# main-01.net
KiCad netlist of a schematic drawn in EAGLE
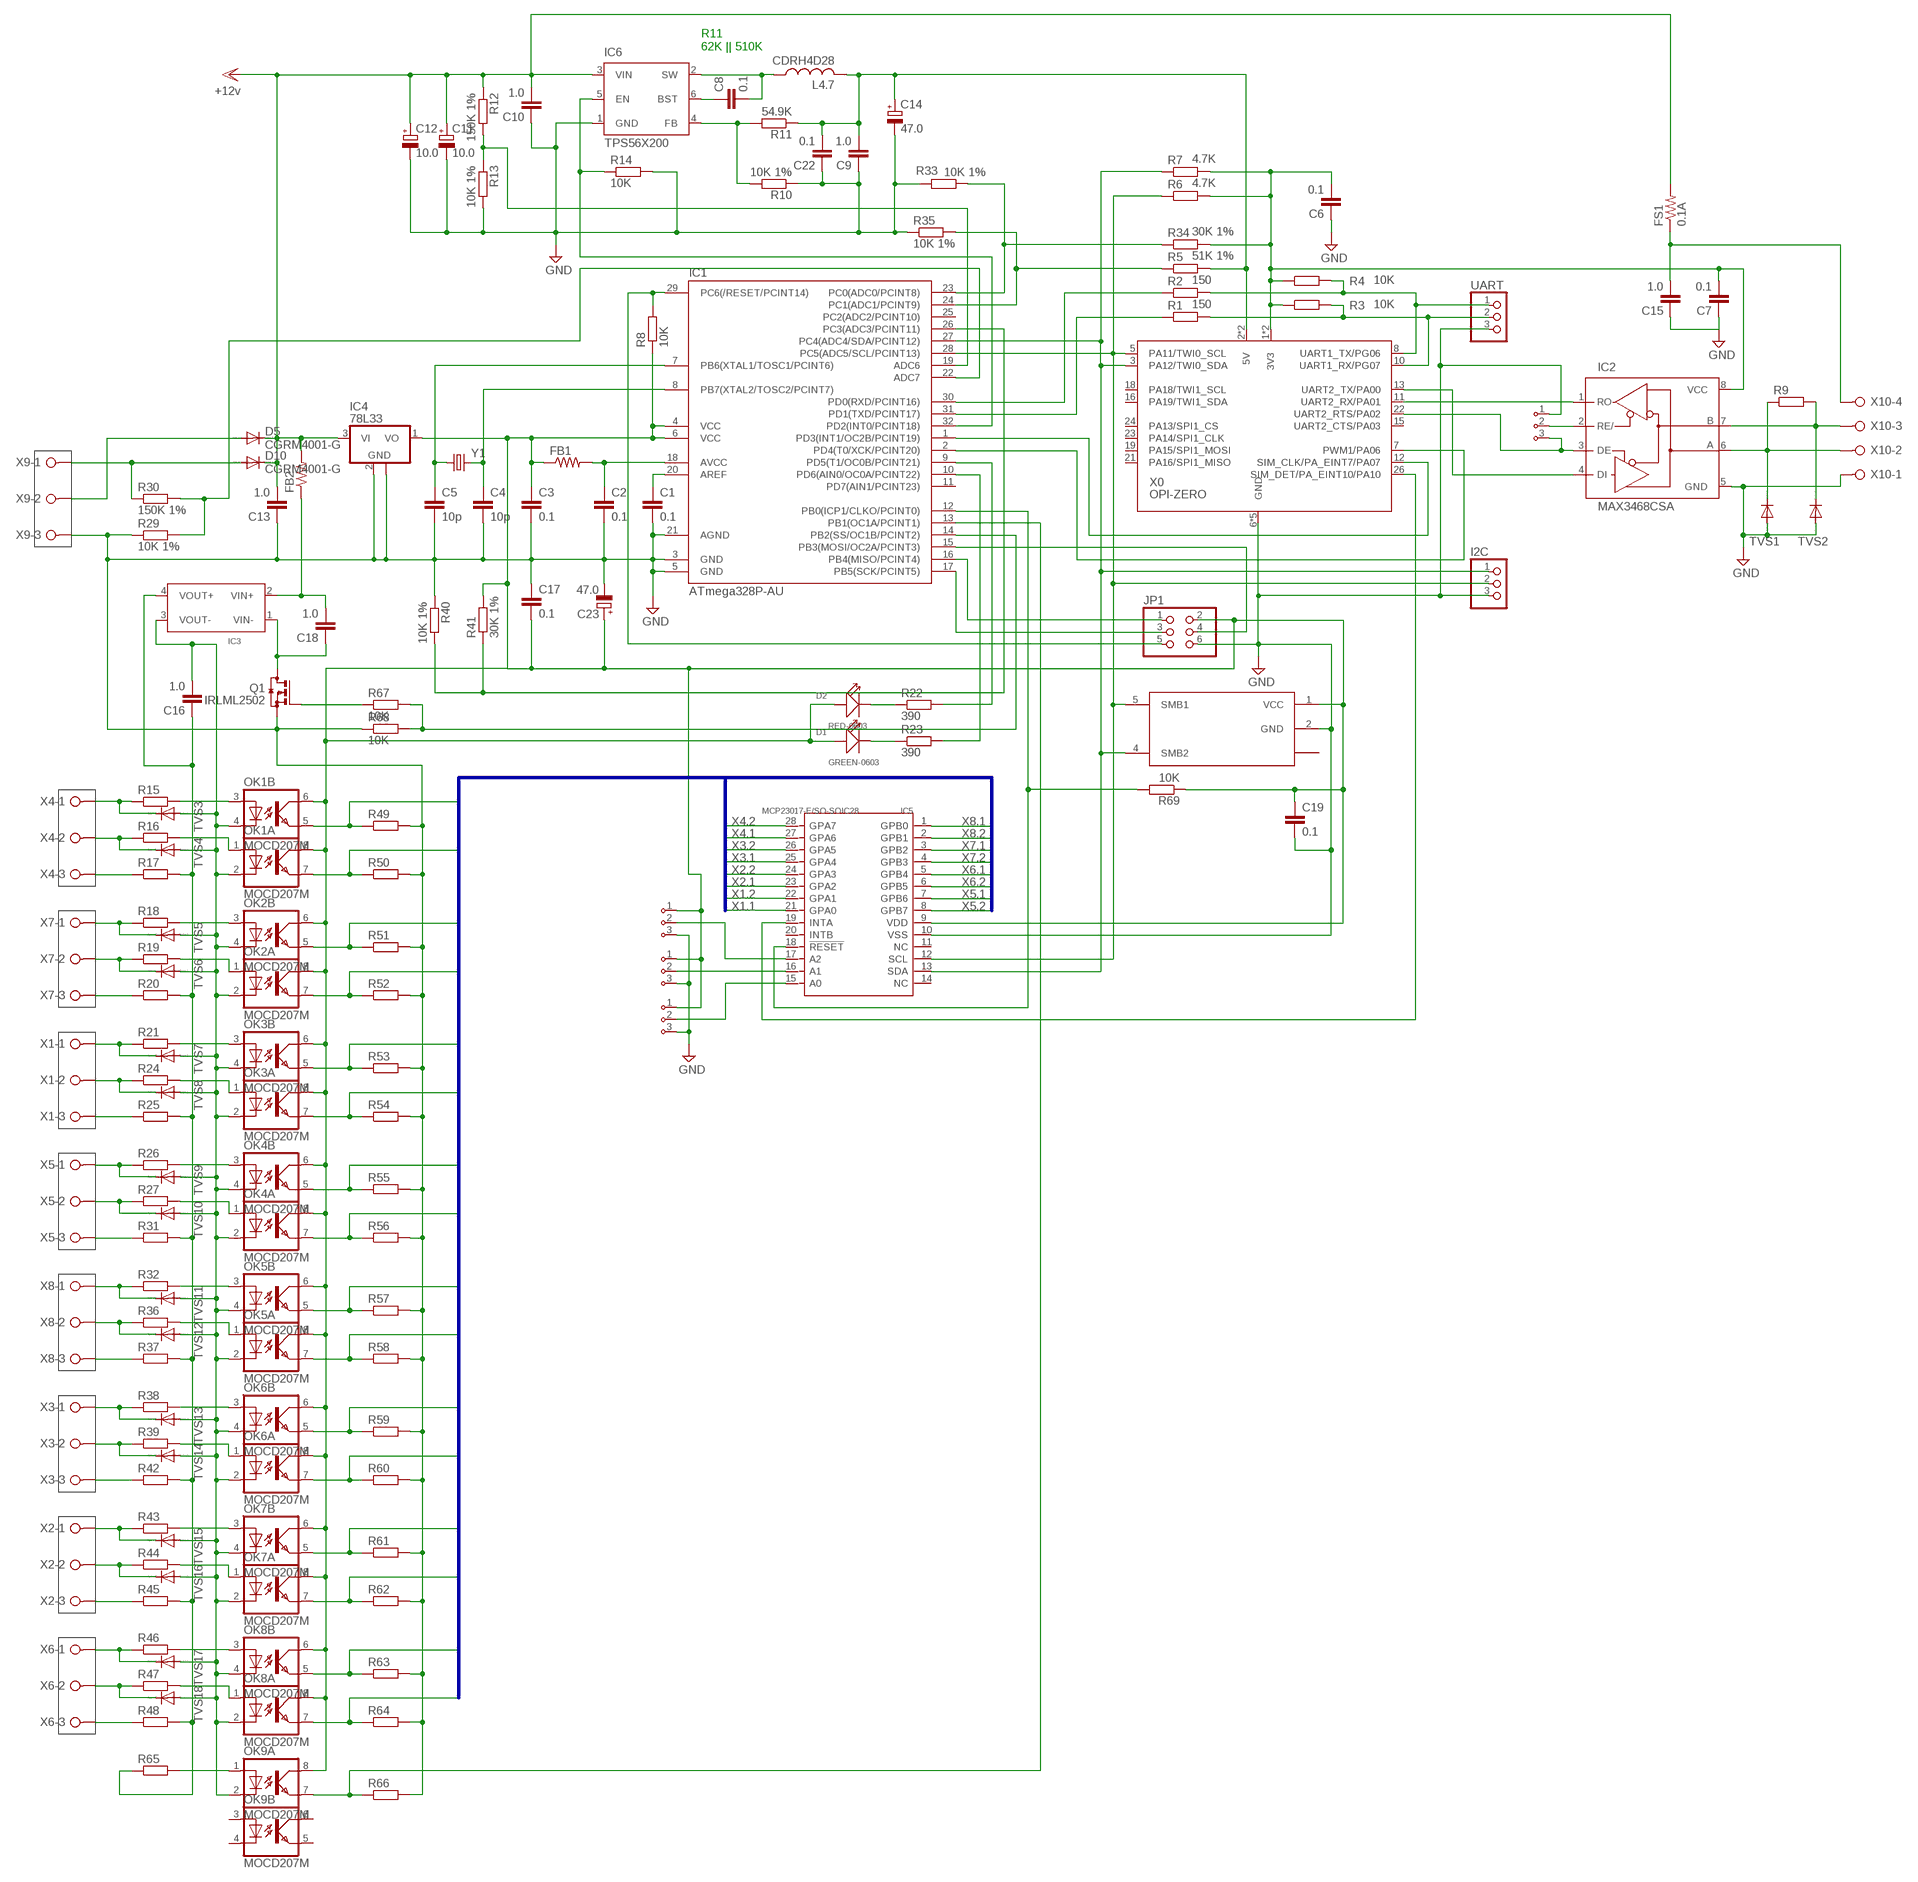
[diagram p0: schematic, sheet 1]

(export (version "E")
  (design (tool "Eeschema 10.0.6"))
  (components
    (comp (ref "4")
      (value "ADDR3PIN0603")
      (footprint "eagle-import:0603-3PIN")
      (libsource (lib "eagle-import") (part "ADDR3PIN0603"))
    )
    (comp (ref "A0")
      (value "ADDR3PIN0603")
      (footprint "eagle-import:0603-3PIN")
      (libsource (lib "eagle-import") (part "ADDR3PIN0603"))
    )
    (comp (ref "A1")
      (value "ADDR3PIN0603")
      (footprint "eagle-import:0603-3PIN")
      (libsource (lib "eagle-import") (part "ADDR3PIN0603"))
    )
    (comp (ref "A2")
      (value "ADDR3PIN0603")
      (footprint "eagle-import:0603-3PIN")
      (libsource (lib "eagle-import") (part "ADDR3PIN0603"))
    )
    (comp (ref "C1")
      (value "0.1")
      (footprint "eagle-import:C0603")
      (libsource (lib "eagle-import") (part "C-EUC0603"))
    )
    (comp (ref "C2")
      (value "0.1")
      (footprint "eagle-import:C0603")
      (libsource (lib "eagle-import") (part "C-EUC0603"))
    )
    (comp (ref "C3")
      (value "0.1")
      (footprint "eagle-import:C0603")
      (libsource (lib "eagle-import") (part "C-EUC0603"))
    )
    (comp (ref "C4")
      (value "10p")
      (footprint "eagle-import:C0603")
      (libsource (lib "eagle-import") (part "C-EUC0603"))
    )
    (comp (ref "C5")
      (value "10p")
      (footprint "eagle-import:C0603")
      (libsource (lib "eagle-import") (part "C-EUC0603"))
    )
    (comp (ref "C6")
      (value "0.1")
      (footprint "eagle-import:C0805")
      (libsource (lib "eagle-import") (part "C-EUC0805"))
    )
    (comp (ref "C7")
      (value "0.1")
      (footprint "eagle-import:C0805")
      (libsource (lib "eagle-import") (part "C-EUC0805"))
    )
    (comp (ref "C8")
      (value "0.1")
      (footprint "eagle-import:C0805")
      (libsource (lib "eagle-import") (part "C-EUC0805"))
    )
    (comp (ref "C9")
      (value "1.0")
      (footprint "eagle-import:C0805")
      (libsource (lib "eagle-import") (part "C-EUC0805"))
    )
    (comp (ref "C10")
      (value "1.0")
      (footprint "eagle-import:C1206")
      (libsource (lib "eagle-import") (part "C-EUC1206"))
    )
    (comp (ref "C11")
      (value "10.0")
      (footprint "eagle-import:C_6032-28R")
      (libsource (lib "eagle-import") (part "CPOL-EUC/6032-28R"))
    )
    (comp (ref "C12")
      (value "10.0")
      (footprint "eagle-import:C_6032-28R")
      (libsource (lib "eagle-import") (part "CPOL-EUC/6032-28R"))
    )
    (comp (ref "C13")
      (value "1.0")
      (footprint "eagle-import:C1206")
      (libsource (lib "eagle-import") (part "C-EUC1206"))
    )
    (comp (ref "C14")
      (value "47.0")
      (footprint "eagle-import:B_3528-21R")
      (libsource (lib "eagle-import") (part "CPOL-EUB/3528-21R"))
    )
    (comp (ref "C15")
      (value "1.0")
      (footprint "eagle-import:C1206")
      (libsource (lib "eagle-import") (part "C-EUC1206"))
    )
    (comp (ref "C16")
      (value "1.0")
      (footprint "eagle-import:C1206")
      (libsource (lib "eagle-import") (part "C-EUC1206"))
    )
    (comp (ref "C17")
      (value "0.1")
      (footprint "eagle-import:C0603")
      (libsource (lib "eagle-import") (part "C-EUC0603"))
    )
    (comp (ref "C18")
      (value "1.0")
      (footprint "eagle-import:C1206")
      (libsource (lib "eagle-import") (part "C-EUC1206"))
    )
    (comp (ref "C19")
      (value "0.1")
      (footprint "eagle-import:C0603")
      (libsource (lib "eagle-import") (part "C-EUC0603"))
    )
    (comp (ref "C22")
      (value "0.1")
      (footprint "eagle-import:C0805")
      (libsource (lib "eagle-import") (part "C-EUC0805"))
    )
    (comp (ref "C23")
      (value "47.0")
      (footprint "eagle-import:B_3528-21R")
      (libsource (lib "eagle-import") (part "CPOL-EUB/3528-21R"))
    )
    (comp (ref "D1")
      (value "GREEN-0603")
      (footprint "eagle-import:LED-0603")
      (fields (field (name "MPN") "19-217-G7C-AN1P2-3T"))
      (libsource (lib "eagle-import") (part "SMD-LED-CLEAR-GREEN(0603)"))
    )
    (comp (ref "D2")
      (value "RED-0603")
      (footprint "eagle-import:LED-0603")
      (fields (field (name "MPN") "19-217-BHC-ZL1M2RY-3T"))
      (libsource (lib "eagle-import") (part "SMD-LED-CLEAR-BLUE(0603)"))
    )
    (comp (ref "D5")
      (value "CGRM4001-G")
      (footprint "eagle-import:SOD-123_MINI-SMA")
      (libsource (lib "eagle-import") (part "CGRM400-G1"))
    )
    (comp (ref "D10")
      (value "CGRM4001-G")
      (footprint "eagle-import:SOD-123_MINI-SMA")
      (libsource (lib "eagle-import") (part "CGRM400-G1"))
    )
    (comp (ref "FB1")
      (value "R-US_R0805")
      (footprint "eagle-import:R0805")
      (libsource (lib "eagle-import") (part "R-US_R0805"))
    )
    (comp (ref "FB2")
      (value "R-US_R1206")
      (footprint "eagle-import:R1206")
      (libsource (lib "eagle-import") (part "R-US_R1206"))
    )
    (comp (ref "FS1")
      (value "0.1A")
      (footprint "eagle-import:R1210")
      (libsource (lib "eagle-import") (part "R-US_R1210"))
    )
    (comp (ref "I2C")
      (value "PINHD-1X3")
      (footprint "eagle-import:1X03")
      (libsource (lib "eagle-import") (part "PINHD-1X3"))
    )
    (comp (ref "IC1")
      (value "ATmega328P-AU")
      (footprint "eagle-import:TQFP32-08")
      (libsource (lib "eagle-import") (part "MEGA48/88/168-AU"))
    )
    (comp (ref "IC2")
      (value "MAX3468CSA")
      (footprint "eagle-import:SO08")
      (fields (field (name "MPN") "MAX3468CSA+"))
      (libsource (lib "eagle-import") (part "MAX34SA68C"))
    )
    (comp (ref "IC3")
      (value "DC-DC-CONV-4PIN-ISOLATINGMURATA-NME-05-12-SERIES")
      (footprint "eagle-import:DC-DC-MURATA-NME-05-12-SERIES")
      (libsource (lib "eagle-import") (part "DC-DC-CONV-4PIN-ISOLATINGMURATA-NME-05-12-SERIES"))
    )
    (comp (ref "IC4")
      (value "78L33")
      (footprint "eagle-import:SOT89")
      (libsource (lib "eagle-import") (part "78LF05"))
    )
    (comp (ref "IC5")
      (value "MCP23017-E/SO-SOIC28")
      (footprint "eagle-import:SOIC28-1.27-17.9X7.5MM")
      (fields (field (name "MPN") "MCP23017-E/SO"))
      (libsource (lib "eagle-import") (part "INTERFACE-MCP23017-E(SOIC28)"))
    )
    (comp (ref "IC6")
      (value "TPS56X200")
      (footprint "eagle-import:TSOT23-6_DDC")
      (libsource (lib "eagle-import") (part "TPS56X200"))
    )
    (comp (ref "IC7")
      (value "LTC1694")
      (footprint "eagle-import:SOT23-5")
      (libsource (lib "eagle-import") (part "LTC1694"))
    )
    (comp (ref "JP1")
      (value "PINHD-2X3")
      (footprint "eagle-import:2X03")
      (libsource (lib "eagle-import") (part "PINHD-2X3"))
    )
    (comp (ref "L4.7")
      (value "CDRH4D28")
      (footprint "eagle-import:CDRH4D28")
      (libsource (lib "eagle-import") (part "CDRH4D28"))
    )
    (comp (ref "OK1")
      (value "MOCD207M")
      (footprint "eagle-import:SOIC08-FAIRCHILD")
      (fields (field (name "MF") "FAIRCHILD SEMICONDUCTOR") (field (name "MPN") "MOCD207-M"))
      (libsource (lib "eagle-import") (part "MOCD20M7"))
    )
    (comp (ref "OK2")
      (value "MOCD207M")
      (footprint "eagle-import:SOIC08-FAIRCHILD")
      (fields (field (name "MF") "FAIRCHILD SEMICONDUCTOR") (field (name "MPN") "MOCD207-M"))
      (libsource (lib "eagle-import") (part "MOCD20M7"))
    )
    (comp (ref "OK3")
      (value "MOCD207M")
      (footprint "eagle-import:SOIC08-FAIRCHILD")
      (fields (field (name "MF") "FAIRCHILD SEMICONDUCTOR") (field (name "MPN") "MOCD207-M"))
      (libsource (lib "eagle-import") (part "MOCD20M7"))
    )
    (comp (ref "OK4")
      (value "MOCD207M")
      (footprint "eagle-import:SOIC08-FAIRCHILD")
      (fields (field (name "MF") "FAIRCHILD SEMICONDUCTOR") (field (name "MPN") "MOCD207-M"))
      (libsource (lib "eagle-import") (part "MOCD20M7"))
    )
    (comp (ref "OK5")
      (value "MOCD207M")
      (footprint "eagle-import:SOIC08-FAIRCHILD")
      (fields (field (name "MF") "FAIRCHILD SEMICONDUCTOR") (field (name "MPN") "MOCD207-M"))
      (libsource (lib "eagle-import") (part "MOCD20M7"))
    )
    (comp (ref "OK6")
      (value "MOCD207M")
      (footprint "eagle-import:SOIC08-FAIRCHILD")
      (fields (field (name "MF") "FAIRCHILD SEMICONDUCTOR") (field (name "MPN") "MOCD207-M"))
      (libsource (lib "eagle-import") (part "MOCD20M7"))
    )
    (comp (ref "OK7")
      (value "MOCD207M")
      (footprint "eagle-import:SOIC08-FAIRCHILD")
      (fields (field (name "MF") "FAIRCHILD SEMICONDUCTOR") (field (name "MPN") "MOCD207-M"))
      (libsource (lib "eagle-import") (part "MOCD20M7"))
    )
    (comp (ref "OK8")
      (value "MOCD207M")
      (footprint "eagle-import:SOIC08-FAIRCHILD")
      (fields (field (name "MF") "FAIRCHILD SEMICONDUCTOR") (field (name "MPN") "MOCD207-M"))
      (libsource (lib "eagle-import") (part "MOCD20M7"))
    )
    (comp (ref "OK9")
      (value "MOCD207M")
      (footprint "eagle-import:SOIC08-FAIRCHILD")
      (fields (field (name "MF") "FAIRCHILD SEMICONDUCTOR") (field (name "MPN") "MOCD207-M"))
      (libsource (lib "eagle-import") (part "MOCD20M7"))
    )
    (comp (ref "Q1")
      (value "IRLML2502")
      (footprint "eagle-import:SOT23")
      (libsource (lib "eagle-import") (part "IRLML2502"))
    )
    (comp (ref "R1")
      (value "150")
      (footprint "eagle-import:R0603")
      (libsource (lib "eagle-import") (part "R-EU_R0603"))
    )
    (comp (ref "R2")
      (value "150")
      (footprint "eagle-import:R0603")
      (libsource (lib "eagle-import") (part "R-EU_R0603"))
    )
    (comp (ref "R3")
      (value "10K")
      (footprint "eagle-import:R0603")
      (libsource (lib "eagle-import") (part "R-EU_R0603"))
    )
    (comp (ref "R4")
      (value "10K")
      (footprint "eagle-import:R0603")
      (libsource (lib "eagle-import") (part "R-EU_R0603"))
    )
    (comp (ref "R5")
      (value "51K 1%")
      (footprint "eagle-import:R0603")
      (libsource (lib "eagle-import") (part "R-EU_R0603"))
    )
    (comp (ref "R6")
      (value "4.7K")
      (footprint "eagle-import:R0603")
      (libsource (lib "eagle-import") (part "R-EU_R0603"))
    )
    (comp (ref "R7")
      (value "4.7K")
      (footprint "eagle-import:R0603")
      (libsource (lib "eagle-import") (part "R-EU_R0603"))
    )
    (comp (ref "R8")
      (value "10K")
      (footprint "eagle-import:R0603")
      (libsource (lib "eagle-import") (part "R-EU_R0603"))
    )
    (comp (ref "R9")
      (value "R-EU_R1206")
      (footprint "eagle-import:R1206")
      (libsource (lib "eagle-import") (part "R-EU_R1206"))
    )
    (comp (ref "R10")
      (value "10K 1%")
      (footprint "eagle-import:R0603")
      (libsource (lib "eagle-import") (part "R-EU_R0603"))
    )
    (comp (ref "R11")
      (value "54.9K")
      (footprint "eagle-import:R0603")
      (libsource (lib "eagle-import") (part "R-EU_R0603"))
    )
    (comp (ref "R12")
      (value "150K 1%")
      (footprint "eagle-import:R0603")
      (libsource (lib "eagle-import") (part "R-EU_R0603"))
    )
    (comp (ref "R13")
      (value "10K 1%")
      (footprint "eagle-import:R0603")
      (libsource (lib "eagle-import") (part "R-EU_R0603"))
    )
    (comp (ref "R14")
      (value "10K")
      (footprint "eagle-import:R0603")
      (libsource (lib "eagle-import") (part "R-EU_R0603"))
    )
    (comp (ref "R15")
      (value "R-EU_R0603")
      (footprint "eagle-import:R0603")
      (libsource (lib "eagle-import") (part "R-EU_R0603"))
    )
    (comp (ref "R16")
      (value "R-EU_R0603")
      (footprint "eagle-import:R0603")
      (libsource (lib "eagle-import") (part "R-EU_R0603"))
    )
    (comp (ref "R17")
      (value "R-EU_R0603")
      (footprint "eagle-import:R0603")
      (libsource (lib "eagle-import") (part "R-EU_R0603"))
    )
    (comp (ref "R18")
      (value "R-EU_R0603")
      (footprint "eagle-import:R0603")
      (libsource (lib "eagle-import") (part "R-EU_R0603"))
    )
    (comp (ref "R19")
      (value "R-EU_R0603")
      (footprint "eagle-import:R0603")
      (libsource (lib "eagle-import") (part "R-EU_R0603"))
    )
    (comp (ref "R20")
      (value "R-EU_R0603")
      (footprint "eagle-import:R0603")
      (libsource (lib "eagle-import") (part "R-EU_R0603"))
    )
    (comp (ref "R21")
      (value "R-EU_R0603")
      (footprint "eagle-import:R0603")
      (libsource (lib "eagle-import") (part "R-EU_R0603"))
    )
    (comp (ref "R22")
      (value "390")
      (footprint "eagle-import:R0603")
      (libsource (lib "eagle-import") (part "R-EU_R0603"))
    )
    (comp (ref "R23")
      (value "390")
      (footprint "eagle-import:R0603")
      (libsource (lib "eagle-import") (part "R-EU_R0603"))
    )
    (comp (ref "R24")
      (value "R-EU_R0603")
      (footprint "eagle-import:R0603")
      (libsource (lib "eagle-import") (part "R-EU_R0603"))
    )
    (comp (ref "R25")
      (value "R-EU_R0603")
      (footprint "eagle-import:R0603")
      (libsource (lib "eagle-import") (part "R-EU_R0603"))
    )
    (comp (ref "R26")
      (value "R-EU_R0603")
      (footprint "eagle-import:R0603")
      (libsource (lib "eagle-import") (part "R-EU_R0603"))
    )
    (comp (ref "R27")
      (value "R-EU_R0603")
      (footprint "eagle-import:R0603")
      (libsource (lib "eagle-import") (part "R-EU_R0603"))
    )
    (comp (ref "R29")
      (value "10K 1%")
      (footprint "eagle-import:R0603")
      (libsource (lib "eagle-import") (part "R-EU_R0603"))
    )
    (comp (ref "R30")
      (value "150K 1%")
      (footprint "eagle-import:R0603")
      (libsource (lib "eagle-import") (part "R-EU_R0603"))
    )
    (comp (ref "R31")
      (value "R-EU_R0603")
      (footprint "eagle-import:R0603")
      (libsource (lib "eagle-import") (part "R-EU_R0603"))
    )
    (comp (ref "R32")
      (value "R-EU_R0603")
      (footprint "eagle-import:R0603")
      (libsource (lib "eagle-import") (part "R-EU_R0603"))
    )
    (comp (ref "R33")
      (value "10K 1%")
      (footprint "eagle-import:R0603")
      (libsource (lib "eagle-import") (part "R-EU_R0603"))
    )
    (comp (ref "R34")
      (value "30K 1%")
      (footprint "eagle-import:R0603")
      (libsource (lib "eagle-import") (part "R-EU_R0603"))
    )
    (comp (ref "R35")
      (value "10K 1%")
      (footprint "eagle-import:R0603")
      (libsource (lib "eagle-import") (part "R-EU_R0603"))
    )
    (comp (ref "R36")
      (value "R-EU_R0603")
      (footprint "eagle-import:R0603")
      (libsource (lib "eagle-import") (part "R-EU_R0603"))
    )
    (comp (ref "R37")
      (value "R-EU_R0603")
      (footprint "eagle-import:R0603")
      (libsource (lib "eagle-import") (part "R-EU_R0603"))
    )
    (comp (ref "R38")
      (value "R-EU_R0603")
      (footprint "eagle-import:R0603")
      (libsource (lib "eagle-import") (part "R-EU_R0603"))
    )
    (comp (ref "R39")
      (value "R-EU_R0603")
      (footprint "eagle-import:R0603")
      (libsource (lib "eagle-import") (part "R-EU_R0603"))
    )
    (comp (ref "R40")
      (value "10K 1%")
      (footprint "eagle-import:R0603")
      (libsource (lib "eagle-import") (part "R-EU_R0603"))
    )
    (comp (ref "R41")
      (value "30K 1%")
      (footprint "eagle-import:R0603")
      (libsource (lib "eagle-import") (part "R-EU_R0603"))
    )
    (comp (ref "R42")
      (value "R-EU_R0603")
      (footprint "eagle-import:R0603")
      (libsource (lib "eagle-import") (part "R-EU_R0603"))
    )
    (comp (ref "R43")
      (value "R-EU_R0603")
      (footprint "eagle-import:R0603")
      (libsource (lib "eagle-import") (part "R-EU_R0603"))
    )
    (comp (ref "R44")
      (value "R-EU_R0603")
      (footprint "eagle-import:R0603")
      (libsource (lib "eagle-import") (part "R-EU_R0603"))
    )
    (comp (ref "R45")
      (value "R-EU_R0603")
      (footprint "eagle-import:R0603")
      (libsource (lib "eagle-import") (part "R-EU_R0603"))
    )
    (comp (ref "R46")
      (value "R-EU_R0603")
      (footprint "eagle-import:R0603")
      (libsource (lib "eagle-import") (part "R-EU_R0603"))
    )
    (comp (ref "R47")
      (value "R-EU_R0603")
      (footprint "eagle-import:R0603")
      (libsource (lib "eagle-import") (part "R-EU_R0603"))
    )
    (comp (ref "R48")
      (value "R-EU_R0603")
      (footprint "eagle-import:R0603")
      (libsource (lib "eagle-import") (part "R-EU_R0603"))
    )
    (comp (ref "R49")
      (value "R-EU_R0603")
      (footprint "eagle-import:R0603")
      (libsource (lib "eagle-import") (part "R-EU_R0603"))
    )
    (comp (ref "R50")
      (value "R-EU_R0603")
      (footprint "eagle-import:R0603")
      (libsource (lib "eagle-import") (part "R-EU_R0603"))
    )
    (comp (ref "R51")
      (value "R-EU_R0603")
      (footprint "eagle-import:R0603")
      (libsource (lib "eagle-import") (part "R-EU_R0603"))
    )
    (comp (ref "R52")
      (value "R-EU_R0603")
      (footprint "eagle-import:R0603")
      (libsource (lib "eagle-import") (part "R-EU_R0603"))
    )
    (comp (ref "R53")
      (value "R-EU_R0603")
      (footprint "eagle-import:R0603")
      (libsource (lib "eagle-import") (part "R-EU_R0603"))
    )
    (comp (ref "R54")
      (value "R-EU_R0603")
      (footprint "eagle-import:R0603")
      (libsource (lib "eagle-import") (part "R-EU_R0603"))
    )
    (comp (ref "R55")
      (value "R-EU_R0603")
      (footprint "eagle-import:R0603")
      (libsource (lib "eagle-import") (part "R-EU_R0603"))
    )
    (comp (ref "R56")
      (value "R-EU_R0603")
      (footprint "eagle-import:R0603")
      (libsource (lib "eagle-import") (part "R-EU_R0603"))
    )
    (comp (ref "R57")
      (value "R-EU_R0603")
      (footprint "eagle-import:R0603")
      (libsource (lib "eagle-import") (part "R-EU_R0603"))
    )
    (comp (ref "R58")
      (value "R-EU_R0603")
      (footprint "eagle-import:R0603")
      (libsource (lib "eagle-import") (part "R-EU_R0603"))
    )
    (comp (ref "R59")
      (value "R-EU_R0603")
      (footprint "eagle-import:R0603")
      (libsource (lib "eagle-import") (part "R-EU_R0603"))
    )
    (comp (ref "R60")
      (value "R-EU_R0603")
      (footprint "eagle-import:R0603")
      (libsource (lib "eagle-import") (part "R-EU_R0603"))
    )
    (comp (ref "R61")
      (value "R-EU_R0603")
      (footprint "eagle-import:R0603")
      (libsource (lib "eagle-import") (part "R-EU_R0603"))
    )
    (comp (ref "R62")
      (value "R-EU_R0603")
      (footprint "eagle-import:R0603")
      (libsource (lib "eagle-import") (part "R-EU_R0603"))
    )
    (comp (ref "R63")
      (value "R-EU_R0603")
      (footprint "eagle-import:R0603")
      (libsource (lib "eagle-import") (part "R-EU_R0603"))
    )
    (comp (ref "R64")
      (value "R-EU_R0603")
      (footprint "eagle-import:R0603")
      (libsource (lib "eagle-import") (part "R-EU_R0603"))
    )
    (comp (ref "R65")
      (value "R-EU_R0603")
      (footprint "eagle-import:R0603")
      (libsource (lib "eagle-import") (part "R-EU_R0603"))
    )
    (comp (ref "R66")
      (value "R-EU_R0603")
      (footprint "eagle-import:R0603")
      (libsource (lib "eagle-import") (part "R-EU_R0603"))
    )
    (comp (ref "R67")
      (value "10K")
      (footprint "eagle-import:R0603")
      (libsource (lib "eagle-import") (part "R-EU_R0603"))
    )
    (comp (ref "R68")
      (value "10K")
      (footprint "eagle-import:R0603")
      (libsource (lib "eagle-import") (part "R-EU_R0603"))
    )
    (comp (ref "R69")
      (value "10K")
      (footprint "eagle-import:R0603")
      (libsource (lib "eagle-import") (part "R-EU_R0603"))
    )
    (comp (ref "TVS1")
      (value "DIODE-SOD323-W")
      (footprint "eagle-import:SOD323-W")
      (libsource (lib "eagle-import") (part "DIODE-SOD323-W"))
    )
    (comp (ref "TVS2")
      (value "DIODE-SOD323-W")
      (footprint "eagle-import:SOD323-W")
      (libsource (lib "eagle-import") (part "DIODE-SOD323-W"))
    )
    (comp (ref "TVS3")
      (value "DIODE-SOD323-W")
      (footprint "eagle-import:SOD323-W")
      (libsource (lib "eagle-import") (part "DIODE-SOD323-W"))
    )
    (comp (ref "TVS4")
      (value "DIODE-SOD323-W")
      (footprint "eagle-import:SOD323-W")
      (libsource (lib "eagle-import") (part "DIODE-SOD323-W"))
    )
    (comp (ref "TVS5")
      (value "DIODE-SOD323-W")
      (footprint "eagle-import:SOD323-W")
      (libsource (lib "eagle-import") (part "DIODE-SOD323-W"))
    )
    (comp (ref "TVS6")
      (value "DIODE-SOD323-W")
      (footprint "eagle-import:SOD323-W")
      (libsource (lib "eagle-import") (part "DIODE-SOD323-W"))
    )
    (comp (ref "TVS7")
      (value "DIODE-SOD323-W")
      (footprint "eagle-import:SOD323-W")
      (libsource (lib "eagle-import") (part "DIODE-SOD323-W"))
    )
    (comp (ref "TVS8")
      (value "DIODE-SOD323-W")
      (footprint "eagle-import:SOD323-W")
      (libsource (lib "eagle-import") (part "DIODE-SOD323-W"))
    )
    (comp (ref "TVS9")
      (value "DIODE-SOD323-W")
      (footprint "eagle-import:SOD323-W")
      (libsource (lib "eagle-import") (part "DIODE-SOD323-W"))
    )
    (comp (ref "TVS10")
      (value "DIODE-SOD323-W")
      (footprint "eagle-import:SOD323-W")
      (libsource (lib "eagle-import") (part "DIODE-SOD323-W"))
    )
    (comp (ref "TVS11")
      (value "DIODE-SOD323-W")
      (footprint "eagle-import:SOD323-W")
      (libsource (lib "eagle-import") (part "DIODE-SOD323-W"))
    )
    (comp (ref "TVS12")
      (value "DIODE-SOD323-W")
      (footprint "eagle-import:SOD323-W")
      (libsource (lib "eagle-import") (part "DIODE-SOD323-W"))
    )
    (comp (ref "TVS13")
      (value "DIODE-SOD323-W")
      (footprint "eagle-import:SOD323-W")
      (libsource (lib "eagle-import") (part "DIODE-SOD323-W"))
    )
    (comp (ref "TVS14")
      (value "DIODE-SOD323-W")
      (footprint "eagle-import:SOD323-W")
      (libsource (lib "eagle-import") (part "DIODE-SOD323-W"))
    )
    (comp (ref "TVS15")
      (value "DIODE-SOD323-W")
      (footprint "eagle-import:SOD323-W")
      (libsource (lib "eagle-import") (part "DIODE-SOD323-W"))
    )
    (comp (ref "TVS16")
      (value "DIODE-SOD323-W")
      (footprint "eagle-import:SOD323-W")
      (libsource (lib "eagle-import") (part "DIODE-SOD323-W"))
    )
    (comp (ref "TVS17")
      (value "DIODE-SOD323-W")
      (footprint "eagle-import:SOD323-W")
      (libsource (lib "eagle-import") (part "DIODE-SOD323-W"))
    )
    (comp (ref "TVS18")
      (value "DIODE-SOD323-W")
      (footprint "eagle-import:SOD323-W")
      (libsource (lib "eagle-import") (part "DIODE-SOD323-W"))
    )
    (comp (ref "UART")
      (value "PINHD-1X3")
      (footprint "eagle-import:1X03")
      (libsource (lib "eagle-import") (part "PINHD-1X3"))
    )
    (comp (ref "X0")
      (value "OPI-ZERO")
      (footprint "eagle-import:OPI0")
      (libsource (lib "eagle-import") (part "OPI-ZERO"))
    )
    (comp (ref "X1")
      (value "W237-03P")
      (footprint "eagle-import:W237-133")
      (libsource (lib "eagle-import") (part "W237-03P"))
    )
    (comp (ref "X2")
      (value "W237-03P")
      (footprint "eagle-import:W237-133")
      (libsource (lib "eagle-import") (part "W237-03P"))
    )
    (comp (ref "X3")
      (value "W237-03P")
      (footprint "eagle-import:W237-133")
      (libsource (lib "eagle-import") (part "W237-03P"))
    )
    (comp (ref "X4")
      (value "W237-03P")
      (footprint "eagle-import:W237-133")
      (libsource (lib "eagle-import") (part "W237-03P"))
    )
    (comp (ref "X5")
      (value "W237-03P")
      (footprint "eagle-import:W237-133")
      (libsource (lib "eagle-import") (part "W237-03P"))
    )
    (comp (ref "X6")
      (value "W237-03P")
      (footprint "eagle-import:W237-133")
      (libsource (lib "eagle-import") (part "W237-03P"))
    )
    (comp (ref "X7")
      (value "W237-03P")
      (footprint "eagle-import:W237-133")
      (libsource (lib "eagle-import") (part "W237-03P"))
    )
    (comp (ref "X8")
      (value "W237-03P")
      (footprint "eagle-import:W237-133")
      (libsource (lib "eagle-import") (part "W237-03P"))
    )
    (comp (ref "X9")
      (value "W237-03P")
      (footprint "eagle-import:W237-133")
      (libsource (lib "eagle-import") (part "W237-03P"))
    )
    (comp (ref "X10")
      (value "W237-04P")
      (footprint "eagle-import:W237-4P")
      (libsource (lib "eagle-import") (part "W237-04P"))
    )
    (comp (ref "Y1")
      (value "CRYSTALHC49US")
      (footprint "eagle-import:HC49US")
      (libsource (lib "eagle-import") (part "CRYSTALHC49US"))
    )
  )
  (nets
    (net (code "1") (name "+12v") (class "Default")
      (node (ref "C10") (pin "2") (pinfunction "2_2") (pintype "passive"))
      (node (ref "C11") (pin "+") (pinfunction "+_+") (pintype "passive"))
      (node (ref "C12") (pin "+") (pinfunction "+_+") (pintype "passive"))
      (node (ref "C13") (pin "2") (pinfunction "2_2") (pintype "passive"))
      (node (ref "D10") (pin "C") (pinfunction "C_C") (pintype "passive"))
      (node (ref "D5") (pin "C") (pinfunction "C_C") (pintype "passive"))
      (node (ref "FB2") (pin "2") (pinfunction "2_2") (pintype "passive"))
      (node (ref "FS1") (pin "2") (pinfunction "2_2") (pintype "passive"))
      (node (ref "IC4") (pin "3") (pinfunction "VI_3") (pintype "input"))
      (node (ref "IC6") (pin "3") (pinfunction "VIN_3") (pintype "input"))
      (node (ref "R12") (pin "1") (pinfunction "1_1") (pintype "passive"))
    )
    (net (code "2") (name "/X1.1") (class "Default")
      (node (ref "IC5") (pin "21") (pinfunction "GPA0_21") (pintype "bidirectional"))
      (node (ref "OK3") (pin "5") (pinfunction "EMIT_5") (pintype "passive"))
      (node (ref "R53") (pin "1") (pinfunction "1_1") (pintype "passive"))
    )
    (net (code "3") (name "/X1.2") (class "Default")
      (node (ref "IC5") (pin "22") (pinfunction "GPA1_22") (pintype "bidirectional"))
      (node (ref "OK3") (pin "7") (pinfunction "EMIT_7") (pintype "passive"))
      (node (ref "R54") (pin "1") (pinfunction "1_1") (pintype "passive"))
    )
    (net (code "4") (name "/X2.1") (class "Default")
      (node (ref "IC5") (pin "23") (pinfunction "GPA2_23") (pintype "bidirectional"))
      (node (ref "OK7") (pin "5") (pinfunction "EMIT_5") (pintype "passive"))
      (node (ref "R61") (pin "1") (pinfunction "1_1") (pintype "passive"))
    )
    (net (code "5") (name "/X2.2") (class "Default")
      (node (ref "IC5") (pin "24") (pinfunction "GPA3_24") (pintype "bidirectional"))
      (node (ref "OK7") (pin "7") (pinfunction "EMIT_7") (pintype "passive"))
      (node (ref "R62") (pin "1") (pinfunction "1_1") (pintype "passive"))
    )
    (net (code "6") (name "/X3.1") (class "Default")
      (node (ref "IC5") (pin "25") (pinfunction "GPA4_25") (pintype "bidirectional"))
      (node (ref "OK6") (pin "5") (pinfunction "EMIT_5") (pintype "passive"))
      (node (ref "R59") (pin "1") (pinfunction "1_1") (pintype "passive"))
    )
    (net (code "7") (name "/X3.2") (class "Default")
      (node (ref "IC5") (pin "26") (pinfunction "GPA5_26") (pintype "bidirectional"))
      (node (ref "OK6") (pin "7") (pinfunction "EMIT_7") (pintype "passive"))
      (node (ref "R60") (pin "1") (pinfunction "1_1") (pintype "passive"))
    )
    (net (code "8") (name "/X4.1") (class "Default")
      (node (ref "IC5") (pin "27") (pinfunction "GPA6_27") (pintype "bidirectional"))
      (node (ref "OK1") (pin "5") (pinfunction "EMIT_5") (pintype "passive"))
      (node (ref "R49") (pin "1") (pinfunction "1_1") (pintype "passive"))
    )
    (net (code "9") (name "/X4.2") (class "Default")
      (node (ref "IC5") (pin "28") (pinfunction "GPA7_28") (pintype "bidirectional"))
      (node (ref "OK1") (pin "7") (pinfunction "EMIT_7") (pintype "passive"))
      (node (ref "R50") (pin "1") (pinfunction "1_1") (pintype "passive"))
    )
    (net (code "10") (name "/X5.1") (class "Default")
      (node (ref "IC5") (pin "7") (pinfunction "GPB6_7") (pintype "bidirectional"))
      (node (ref "OK4") (pin "5") (pinfunction "EMIT_5") (pintype "passive"))
      (node (ref "R55") (pin "1") (pinfunction "1_1") (pintype "passive"))
    )
    (net (code "11") (name "/X5.2") (class "Default")
      (node (ref "IC5") (pin "8") (pinfunction "GPB7_8") (pintype "bidirectional"))
      (node (ref "OK4") (pin "7") (pinfunction "EMIT_7") (pintype "passive"))
      (node (ref "R56") (pin "1") (pinfunction "1_1") (pintype "passive"))
    )
    (net (code "12") (name "/X6.1") (class "Default")
      (node (ref "IC5") (pin "5") (pinfunction "GPB4_5") (pintype "bidirectional"))
      (node (ref "OK8") (pin "5") (pinfunction "EMIT_5") (pintype "passive"))
      (node (ref "R63") (pin "1") (pinfunction "1_1") (pintype "passive"))
    )
    (net (code "13") (name "/X6.2") (class "Default")
      (node (ref "IC5") (pin "6") (pinfunction "GPB5_6") (pintype "bidirectional"))
      (node (ref "OK8") (pin "7") (pinfunction "EMIT_7") (pintype "passive"))
      (node (ref "R64") (pin "1") (pinfunction "1_1") (pintype "passive"))
    )
    (net (code "14") (name "/X7.1") (class "Default")
      (node (ref "IC5") (pin "3") (pinfunction "GPB2_3") (pintype "bidirectional"))
      (node (ref "OK2") (pin "5") (pinfunction "EMIT_5") (pintype "passive"))
      (node (ref "R51") (pin "1") (pinfunction "1_1") (pintype "passive"))
    )
    (net (code "15") (name "/X7.2") (class "Default")
      (node (ref "IC5") (pin "4") (pinfunction "GPB3_4") (pintype "bidirectional"))
      (node (ref "OK2") (pin "7") (pinfunction "EMIT_7") (pintype "passive"))
      (node (ref "R52") (pin "1") (pinfunction "1_1") (pintype "passive"))
    )
    (net (code "16") (name "/X8.1") (class "Default")
      (node (ref "IC5") (pin "1") (pinfunction "GPB0_1") (pintype "bidirectional"))
      (node (ref "OK5") (pin "5") (pinfunction "EMIT_5") (pintype "passive"))
      (node (ref "R57") (pin "1") (pinfunction "1_1") (pintype "passive"))
    )
    (net (code "17") (name "/X8.2") (class "Default")
      (node (ref "IC5") (pin "2") (pinfunction "GPB1_2") (pintype "bidirectional"))
      (node (ref "OK5") (pin "7") (pinfunction "EMIT_7") (pintype "passive"))
      (node (ref "R58") (pin "1") (pinfunction "1_1") (pintype "passive"))
    )
    (net (code "18") (name "GND") (class "Default")
      (node (ref "4") (pin "1") (pinfunction "P$2_1") (pintype "power_in"))
      (node (ref "A0") (pin "3") (pinfunction "P$3_3") (pintype "power_in"))
      (node (ref "A1") (pin "3") (pinfunction "P$3_3") (pintype "power_in"))
      (node (ref "A2") (pin "3") (pinfunction "P$3_3") (pintype "power_in"))
      (node (ref "C1") (pin "2") (pinfunction "2_2") (pintype "passive"))
      (node (ref "C10") (pin "1") (pinfunction "1_1") (pintype "passive"))
      (node (ref "C11") (pin "-") (pinfunction "-_-") (pintype "passive"))
      (node (ref "C12") (pin "-") (pinfunction "-_-") (pintype "passive"))
      (node (ref "C13") (pin "1") (pinfunction "1_1") (pintype "passive"))
      (node (ref "C14") (pin "-") (pinfunction "-_-") (pintype "passive"))
      (node (ref "C15") (pin "1") (pinfunction "1_1") (pintype "passive"))
      (node (ref "C17") (pin "1") (pinfunction "1_1") (pintype "passive"))
      (node (ref "C19") (pin "2") (pinfunction "2_2") (pintype "passive"))
      (node (ref "C2") (pin "2") (pinfunction "2_2") (pintype "passive"))
      (node (ref "C22") (pin "1") (pinfunction "1_1") (pintype "passive"))
      (node (ref "C23") (pin "-") (pinfunction "-_-") (pintype "passive"))
      (node (ref "C3") (pin "2") (pinfunction "2_2") (pintype "passive"))
      (node (ref "C4") (pin "2") (pinfunction "2_2") (pintype "passive"))
      (node (ref "C5") (pin "2") (pinfunction "2_2") (pintype "passive"))
      (node (ref "C6") (pin "1") (pinfunction "1_1") (pintype "passive"))
      (node (ref "C7") (pin "1") (pinfunction "1_1") (pintype "passive"))
      (node (ref "C9") (pin "1") (pinfunction "1_1") (pintype "passive"))
      (node (ref "I2C") (pin "3") (pinfunction "3_3") (pintype "passive"))
      (node (ref "IC1") (pin "21") (pinfunction "AGND_21") (pintype "power_in"))
      (node (ref "IC1") (pin "3") (pinfunction "GND_3") (pintype "power_in"))
      (node (ref "IC1") (pin "5") (pinfunction "GND_5") (pintype "power_in"))
      (node (ref "IC2") (pin "5") (pinfunction "GND_5") (pintype "power_in"))
      (node (ref "IC4") (pin "2") (pinfunction "GND_2") (pintype "passive"))
      (node (ref "IC4") (pin "2@1") (pinfunction "GND_2@1") (pintype "passive"))
      (node (ref "IC5") (pin "10") (pinfunction "VSS_10") (pintype "bidirectional"))
      (node (ref "IC6") (pin "1") (pinfunction "GND_1") (pintype "power_in"))
      (node (ref "IC7") (pin "2") (pinfunction "GND_2") (pintype "power_in"))
      (node (ref "JP1") (pin "6") (pinfunction "6_6") (pintype "passive"))
      (node (ref "Q1") (pin "2") (pinfunction "S_2") (pintype "passive"))
      (node (ref "R10") (pin "1") (pinfunction "1_1") (pintype "passive"))
      (node (ref "R13") (pin "2") (pinfunction "2_2") (pintype "passive"))
      (node (ref "R14") (pin "2") (pinfunction "2_2") (pintype "passive"))
      (node (ref "R29") (pin "1") (pinfunction "1_1") (pintype "passive"))
      (node (ref "R33") (pin "2") (pinfunction "2_2") (pintype "passive"))
      (node (ref "R35") (pin "1") (pinfunction "1_1") (pintype "passive"))
      (node (ref "R40") (pin "1") (pinfunction "1_1") (pintype "passive"))
      (node (ref "R49") (pin "2") (pinfunction "2_2") (pintype "passive"))
      (node (ref "R50") (pin "2") (pinfunction "2_2") (pintype "passive"))
      (node (ref "R51") (pin "2") (pinfunction "2_2") (pintype "passive"))
      (node (ref "R52") (pin "2") (pinfunction "2_2") (pintype "passive"))
      (node (ref "R53") (pin "2") (pinfunction "2_2") (pintype "passive"))
      (node (ref "R54") (pin "2") (pinfunction "2_2") (pintype "passive"))
      (node (ref "R55") (pin "2") (pinfunction "2_2") (pintype "passive"))
      (node (ref "R56") (pin "2") (pinfunction "2_2") (pintype "passive"))
      (node (ref "R57") (pin "2") (pinfunction "2_2") (pintype "passive"))
      (node (ref "R58") (pin "2") (pinfunction "2_2") (pintype "passive"))
      (node (ref "R59") (pin "2") (pinfunction "2_2") (pintype "passive"))
      (node (ref "R60") (pin "2") (pinfunction "2_2") (pintype "passive"))
      (node (ref "R61") (pin "2") (pinfunction "2_2") (pintype "passive"))
      (node (ref "R62") (pin "2") (pinfunction "2_2") (pintype "passive"))
      (node (ref "R63") (pin "2") (pinfunction "2_2") (pintype "passive"))
      (node (ref "R64") (pin "2") (pinfunction "2_2") (pintype "passive"))
      (node (ref "R66") (pin "2") (pinfunction "2_2") (pintype "passive"))
      (node (ref "R68") (pin "1") (pinfunction "1_1") (pintype "passive"))
      (node (ref "TVS1") (pin "A") (pinfunction "A_A") (pintype "passive"))
      (node (ref "TVS2") (pin "A") (pinfunction "A_A") (pintype "passive"))
      (node (ref "UART") (pin "3") (pinfunction "3_3") (pintype "passive"))
      (node (ref "X0") (pin "14") (pinfunction "GND_14") (pintype "power_in"))
      (node (ref "X0") (pin "20") (pinfunction "GND_20") (pintype "power_in"))
      (node (ref "X0") (pin "25") (pinfunction "GND_25") (pintype "power_in"))
      (node (ref "X0") (pin "6") (pinfunction "GND_6") (pintype "power_in"))
      (node (ref "X0") (pin "9") (pinfunction "GND_9") (pintype "power_in"))
      (node (ref "X10") (pin "1") (pinfunction "KL_1") (pintype "passive"))
      (node (ref "X9") (pin "3") (pinfunction "KL_3") (pintype "passive"))
    )
    (net (code "19") (name "Net-(4-P$1)") (class "Default")
      (node (ref "4") (pin "2") (pinfunction "P$1_2") (pintype "bidirectional"))
      (node (ref "IC2") (pin "2") (pinfunction "RE/_2") (pintype "input"))
    )
    (net (code "20") (name "Net-(4-P$3)") (class "Default")
      (node (ref "4") (pin "3") (pinfunction "P$3_3") (pintype "power_in"))
      (node (ref "IC2") (pin "3") (pinfunction "DE_3") (pintype "input"))
      (node (ref "X0") (pin "22") (pinfunction "UART2_RTS/PA02_22") (pintype "bidirectional"))
    )
    (net (code "21") (name "Net-(A0-P$1)") (class "Default")
      (node (ref "A0") (pin "2") (pinfunction "P$1_2") (pintype "bidirectional"))
      (node (ref "IC5") (pin "15") (pinfunction "A0_15") (pintype "bidirectional"))
    )
    (net (code "22") (name "Net-(A0-P$2)") (class "Default")
      (node (ref "A0") (pin "1") (pinfunction "P$2_1") (pintype "power_in"))
      (node (ref "A1") (pin "1") (pinfunction "P$2_1") (pintype "power_in"))
      (node (ref "A2") (pin "1") (pinfunction "P$2_1") (pintype "power_in"))
      (node (ref "C17") (pin "2") (pinfunction "2_2") (pintype "passive"))
      (node (ref "C19") (pin "1") (pinfunction "1_1") (pintype "passive"))
      (node (ref "C23") (pin "+") (pinfunction "+_+") (pintype "passive"))
      (node (ref "C3") (pin "1") (pinfunction "1_1") (pintype "passive"))
      (node (ref "D1") (pin "+") (pinfunction "+_+") (pintype "passive"))
      (node (ref "D2") (pin "+") (pinfunction "+_+") (pintype "passive"))
      (node (ref "FB1") (pin "1") (pinfunction "1_1") (pintype "passive"))
      (node (ref "IC1") (pin "4") (pinfunction "VCC_4") (pintype "power_in"))
      (node (ref "IC1") (pin "6") (pinfunction "VCC_6") (pintype "power_in"))
      (node (ref "IC4") (pin "1") (pinfunction "VO_1") (pintype "passive"))
      (node (ref "IC5") (pin "9") (pinfunction "VDD_9") (pintype "bidirectional"))
      (node (ref "IC7") (pin "1") (pinfunction "VCC_1") (pintype "power_in"))
      (node (ref "JP1") (pin "2") (pinfunction "2_2") (pintype "passive"))
      (node (ref "OK1") (pin "6") (pinfunction "COL_6") (pintype "passive"))
      (node (ref "OK1") (pin "8") (pinfunction "COL_8") (pintype "passive"))
      (node (ref "OK2") (pin "6") (pinfunction "COL_6") (pintype "passive"))
      (node (ref "OK2") (pin "8") (pinfunction "COL_8") (pintype "passive"))
      (node (ref "OK3") (pin "6") (pinfunction "COL_6") (pintype "passive"))
      (node (ref "OK3") (pin "8") (pinfunction "COL_8") (pintype "passive"))
      (node (ref "OK4") (pin "6") (pinfunction "COL_6") (pintype "passive"))
      (node (ref "OK4") (pin "8") (pinfunction "COL_8") (pintype "passive"))
      (node (ref "OK5") (pin "6") (pinfunction "COL_6") (pintype "passive"))
      (node (ref "OK5") (pin "8") (pinfunction "COL_8") (pintype "passive"))
      (node (ref "OK6") (pin "6") (pinfunction "COL_6") (pintype "passive"))
      (node (ref "OK6") (pin "8") (pinfunction "COL_8") (pintype "passive"))
      (node (ref "OK7") (pin "6") (pinfunction "COL_6") (pintype "passive"))
      (node (ref "OK7") (pin "8") (pinfunction "COL_8") (pintype "passive"))
      (node (ref "OK8") (pin "6") (pinfunction "COL_6") (pintype "passive"))
      (node (ref "OK8") (pin "8") (pinfunction "COL_8") (pintype "passive"))
      (node (ref "OK9") (pin "8") (pinfunction "COL_8") (pintype "passive"))
      (node (ref "R41") (pin "2") (pinfunction "2_2") (pintype "passive"))
      (node (ref "R69") (pin "1") (pinfunction "1_1") (pintype "passive"))
      (node (ref "R8") (pin "1") (pinfunction "1_1") (pintype "passive"))
    )
    (net (code "23") (name "Net-(A1-P$1)") (class "Default")
      (node (ref "A1") (pin "2") (pinfunction "P$1_2") (pintype "bidirectional"))
      (node (ref "IC5") (pin "16") (pinfunction "A1_16") (pintype "bidirectional"))
    )
    (net (code "24") (name "Net-(A2-P$1)") (class "Default")
      (node (ref "A2") (pin "2") (pinfunction "P$1_2") (pintype "bidirectional"))
      (node (ref "IC5") (pin "17") (pinfunction "A2_17") (pintype "bidirectional"))
    )
    (net (code "25") (name "Net-(D1-Pad-)") (class "Default")
      (node (ref "D1") (pin "-") (pinfunction "-_-") (pintype "passive"))
      (node (ref "R23") (pin "1") (pinfunction "1_1") (pintype "passive"))
    )
    (net (code "26") (name "Net-(D2-Pad-)") (class "Default")
      (node (ref "D2") (pin "-") (pinfunction "-_-") (pintype "passive"))
      (node (ref "R22") (pin "1") (pinfunction "1_1") (pintype "passive"))
    )
    (net (code "27") (name "Net-(IC1-ADC6)") (class "Default")
      (node (ref "IC1") (pin "19") (pinfunction "ADC6_19") (pintype "passive"))
      (node (ref "R12") (pin "2") (pinfunction "2_2") (pintype "passive"))
      (node (ref "R13") (pin "1") (pinfunction "1_1") (pintype "passive"))
    )
    (net (code "28") (name "Net-(IC1-ADC7)") (class "Default")
      (node (ref "IC1") (pin "22") (pinfunction "ADC7_22") (pintype "passive"))
      (node (ref "R29") (pin "2") (pinfunction "2_2") (pintype "passive"))
      (node (ref "R30") (pin "2") (pinfunction "2_2") (pintype "passive"))
    )
    (net (code "29") (name "Net-(IC1-AREF)") (class "Default")
      (node (ref "C1") (pin "1") (pinfunction "1_1") (pintype "passive"))
      (node (ref "IC1") (pin "20") (pinfunction "AREF_20") (pintype "passive"))
    )
    (net (code "30") (name "Net-(IC1-AVCC)") (class "Default")
      (node (ref "C2") (pin "1") (pinfunction "1_1") (pintype "passive"))
      (node (ref "FB1") (pin "2") (pinfunction "2_2") (pintype "passive"))
      (node (ref "IC1") (pin "18") (pinfunction "AVCC_18") (pintype "passive"))
    )
    (net (code "31") (name "Net-(IC1-PB0(ICP1{slash}CLKO{slash}PCINT0))") (class "Default")
      (node (ref "IC1") (pin "12") (pinfunction "PB0(ICP1/CLKO/PCINT0)_12") (pintype "bidirectional"))
      (node (ref "IC5") (pin "18") (pinfunction "~{RESET}_18") (pintype "bidirectional"))
      (node (ref "R69") (pin "2") (pinfunction "2_2") (pintype "passive"))
    )
    (net (code "32") (name "Net-(IC1-PB1(OC1A{slash}PCINT1))") (class "Default")
      (node (ref "IC1") (pin "13") (pinfunction "PB1(OC1A/PCINT1)_13") (pintype "bidirectional"))
      (node (ref "OK9") (pin "7") (pinfunction "EMIT_7") (pintype "passive"))
      (node (ref "R66") (pin "1") (pinfunction "1_1") (pintype "passive"))
    )
    (net (code "33") (name "Net-(IC1-PB2(SS{slash}OC1B{slash}PCINT2))") (class "Default")
      (node (ref "IC1") (pin "14") (pinfunction "PB2(SS/OC1B/PCINT2)_14") (pintype "bidirectional"))
      (node (ref "R67") (pin "2") (pinfunction "2_2") (pintype "passive"))
      (node (ref "R68") (pin "2") (pinfunction "2_2") (pintype "passive"))
    )
    (net (code "34") (name "Net-(IC1-PB3(MOSI{slash}OC2A{slash}PCINT3))") (class "Default")
      (node (ref "IC1") (pin "15") (pinfunction "PB3(MOSI/OC2A/PCINT3)_15") (pintype "bidirectional"))
      (node (ref "JP1") (pin "4") (pinfunction "4_4") (pintype "passive"))
    )
    (net (code "35") (name "Net-(IC1-PB4(MISO{slash}PCINT4))") (class "Default")
      (node (ref "IC1") (pin "16") (pinfunction "PB4(MISO/PCINT4)_16") (pintype "bidirectional"))
      (node (ref "JP1") (pin "1") (pinfunction "1_1") (pintype "passive"))
    )
    (net (code "36") (name "Net-(IC1-PB5(SCK{slash}PCINT5))") (class "Default")
      (node (ref "IC1") (pin "17") (pinfunction "PB5(SCK/PCINT5)_17") (pintype "bidirectional"))
      (node (ref "JP1") (pin "3") (pinfunction "3_3") (pintype "passive"))
    )
    (net (code "37") (name "Net-(IC1-PB6(XTAL1{slash}TOSC1{slash}PCINT6))") (class "Default")
      (node (ref "C5") (pin "1") (pinfunction "1_1") (pintype "passive"))
      (node (ref "IC1") (pin "7") (pinfunction "PB6(XTAL1/TOSC1/PCINT6)_7") (pintype "bidirectional"))
      (node (ref "Y1") (pin "1") (pinfunction "1_1") (pintype "passive"))
    )
    (net (code "38") (name "Net-(IC1-PB7(XTAL2{slash}TOSC2{slash}PCINT7))") (class "Default")
      (node (ref "C4") (pin "1") (pinfunction "1_1") (pintype "passive"))
      (node (ref "IC1") (pin "8") (pinfunction "PB7(XTAL2/TOSC2/PCINT7)_8") (pintype "bidirectional"))
      (node (ref "Y1") (pin "2") (pinfunction "2_2") (pintype "passive"))
    )
    (net (code "39") (name "Net-(IC1-PC0(ADC0{slash}PCINT8))") (class "Default")
      (node (ref "IC1") (pin "23") (pinfunction "PC0(ADC0/PCINT8)_23") (pintype "bidirectional"))
      (node (ref "R33") (pin "1") (pinfunction "1_1") (pintype "passive"))
      (node (ref "R34") (pin "1") (pinfunction "1_1") (pintype "passive"))
    )
    (net (code "40") (name "Net-(IC1-PC1(ADC1{slash}PCINT9))") (class "Default")
      (node (ref "IC1") (pin "24") (pinfunction "PC1(ADC1/PCINT9)_24") (pintype "bidirectional"))
      (node (ref "R35") (pin "2") (pinfunction "2_2") (pintype "passive"))
      (node (ref "R5") (pin "1") (pinfunction "1_1") (pintype "passive"))
    )
    (net (code "41") (name "Net-(IC1-PC3(ADC3{slash}PCINT11))") (class "Default")
      (node (ref "IC1") (pin "26") (pinfunction "PC3(ADC3/PCINT11)_26") (pintype "bidirectional"))
      (node (ref "R40") (pin "2") (pinfunction "2_2") (pintype "passive"))
      (node (ref "R41") (pin "1") (pinfunction "1_1") (pintype "passive"))
    )
    (net (code "42") (name "Net-(IC1-PC4(ADC4{slash}SDA{slash}PCINT12))") (class "Default")
      (node (ref "I2C") (pin "1") (pinfunction "1_1") (pintype "passive"))
      (node (ref "IC1") (pin "27") (pinfunction "PC4(ADC4/SDA/PCINT12)_27") (pintype "bidirectional"))
      (node (ref "IC5") (pin "13") (pinfunction "SDA_13") (pintype "bidirectional"))
      (node (ref "IC7") (pin "4") (pinfunction "SMB2_4") (pintype "bidirectional"))
      (node (ref "R7") (pin "1") (pinfunction "1_1") (pintype "passive"))
      (node (ref "X0") (pin "3") (pinfunction "PA12/TWI0_SDA_3") (pintype "bidirectional"))
    )
    (net (code "43") (name "Net-(IC1-PC5(ADC5{slash}SCL{slash}PCINT13))") (class "Default")
      (node (ref "I2C") (pin "2") (pinfunction "2_2") (pintype "passive"))
      (node (ref "IC1") (pin "28") (pinfunction "PC5(ADC5/SCL/PCINT13)_28") (pintype "bidirectional"))
      (node (ref "IC5") (pin "12") (pinfunction "SCL_12") (pintype "bidirectional"))
      (node (ref "IC7") (pin "5") (pinfunction "SMB1_5") (pintype "bidirectional"))
      (node (ref "R6") (pin "1") (pinfunction "1_1") (pintype "passive"))
      (node (ref "X0") (pin "5") (pinfunction "PA11/TWI0_SCL_5") (pintype "bidirectional"))
    )
    (net (code "44") (name "Net-(IC1-PC6({slash}RESET{slash}PCINT14))") (class "Default")
      (node (ref "IC1") (pin "29") (pinfunction "PC6(/RESET/PCINT14)_29") (pintype "bidirectional"))
      (node (ref "JP1") (pin "5") (pinfunction "5_5") (pintype "passive"))
      (node (ref "R8") (pin "2") (pinfunction "2_2") (pintype "passive"))
    )
    (net (code "45") (name "Net-(IC1-PD0(RXD{slash}PCINT16))") (class "Default")
      (node (ref "IC1") (pin "30") (pinfunction "PD0(RXD/PCINT16)_30") (pintype "bidirectional"))
      (node (ref "R2") (pin "1") (pinfunction "1_1") (pintype "passive"))
    )
    (net (code "46") (name "Net-(IC1-PD1(TXD{slash}PCINT17))") (class "Default")
      (node (ref "IC1") (pin "31") (pinfunction "PD1(TXD/PCINT17)_31") (pintype "bidirectional"))
      (node (ref "R1") (pin "1") (pinfunction "1_1") (pintype "passive"))
    )
    (net (code "47") (name "Net-(IC1-PD2(INT0{slash}PCINT18))") (class "Default")
      (node (ref "IC1") (pin "32") (pinfunction "PD2(INT0/PCINT18)_32") (pintype "bidirectional"))
      (node (ref "IC6") (pin "5") (pinfunction "EN_5") (pintype "input"))
      (node (ref "R14") (pin "1") (pinfunction "1_1") (pintype "passive"))
    )
    (net (code "48") (name "Net-(IC1-PD3(INT1{slash}OC2B{slash}PCINT19))") (class "Default")
      (node (ref "IC1") (pin "1") (pinfunction "PD3(INT1/OC2B/PCINT19)_1") (pintype "bidirectional"))
      (node (ref "X0") (pin "12") (pinfunction "SIM_CLK/PA_EINT7/PA07_12") (pintype "bidirectional"))
    )
    (net (code "49") (name "Net-(IC1-PD4(T0{slash}XCK{slash}PCINT20))") (class "Default")
      (node (ref "IC1") (pin "2") (pinfunction "PD4(T0/XCK/PCINT20)_2") (pintype "bidirectional"))
      (node (ref "X0") (pin "7") (pinfunction "PWM1/PA06_7") (pintype "bidirectional"))
    )
    (net (code "50") (name "Net-(IC1-PD5(T1{slash}OC0B{slash}PCINT21))") (class "Default")
      (node (ref "IC1") (pin "9") (pinfunction "PD5(T1/OC0B/PCINT21)_9") (pintype "bidirectional"))
      (node (ref "R22") (pin "2") (pinfunction "2_2") (pintype "passive"))
    )
    (net (code "51") (name "Net-(IC1-PD6(AIN0{slash}OC0A{slash}PCINT22))") (class "Default")
      (node (ref "IC1") (pin "10") (pinfunction "PD6(AIN0/OC0A/PCINT22)_10") (pintype "bidirectional"))
      (node (ref "R23") (pin "2") (pinfunction "2_2") (pintype "passive"))
    )
    (net (code "52") (name "Net-(IC2-A)") (class "Default")
      (node (ref "IC2") (pin "6") (pinfunction "A_6") (pintype "passive"))
      (node (ref "R9") (pin "1") (pinfunction "1_1") (pintype "passive"))
      (node (ref "TVS1") (pin "C") (pinfunction "C_C") (pintype "passive"))
      (node (ref "X10") (pin "2") (pinfunction "KL_2") (pintype "passive"))
    )
    (net (code "53") (name "Net-(IC2-B)") (class "Default")
      (node (ref "IC2") (pin "7") (pinfunction "B_7") (pintype "passive"))
      (node (ref "R9") (pin "2") (pinfunction "2_2") (pintype "passive"))
      (node (ref "TVS2") (pin "C") (pinfunction "C_C") (pintype "passive"))
      (node (ref "X10") (pin "3") (pinfunction "KL_3") (pintype "passive"))
    )
    (net (code "54") (name "Net-(IC2-DI)") (class "Default")
      (node (ref "IC2") (pin "4") (pinfunction "DI_4") (pintype "input"))
      (node (ref "X0") (pin "13") (pinfunction "UART2_TX/PA00_13") (pintype "bidirectional"))
    )
    (net (code "55") (name "Net-(IC2-RO)") (class "Default")
      (node (ref "IC2") (pin "1") (pinfunction "RO_1") (pintype "output"))
      (node (ref "X0") (pin "11") (pinfunction "UART2_RX/PA01_11") (pintype "bidirectional"))
    )
    (net (code "56") (name "Net-(IC2-VCC)") (class "Default")
      (node (ref "C6") (pin "2") (pinfunction "2_2") (pintype "passive"))
      (node (ref "C7") (pin "2") (pinfunction "2_2") (pintype "passive"))
      (node (ref "IC2") (pin "8") (pinfunction "VCC_8") (pintype "power_in"))
      (node (ref "R3") (pin "1") (pinfunction "1_1") (pintype "passive"))
      (node (ref "R34") (pin "2") (pinfunction "2_2") (pintype "passive"))
      (node (ref "R4") (pin "1") (pinfunction "1_1") (pintype "passive"))
      (node (ref "R6") (pin "2") (pinfunction "2_2") (pintype "passive"))
      (node (ref "R7") (pin "2") (pinfunction "2_2") (pintype "passive"))
      (node (ref "X0") (pin "1") (pinfunction "3V3_1") (pintype "power_in"))
      (node (ref "X0") (pin "17") (pinfunction "3V3_17") (pintype "power_in"))
    )
    (net (code "57") (name "Net-(IC3-VIN+)") (class "Default")
      (node (ref "C18") (pin "2") (pinfunction "2_2") (pintype "passive"))
      (node (ref "FB2") (pin "1") (pinfunction "1_1") (pintype "passive"))
      (node (ref "IC3") (pin "2") (pinfunction "VIN+_2") (pintype "bidirectional"))
    )
    (net (code "58") (name "Net-(IC3-VIN-)") (class "Default")
      (node (ref "C18") (pin "1") (pinfunction "1_1") (pintype "passive"))
      (node (ref "IC3") (pin "1") (pinfunction "VIN-_1") (pintype "bidirectional"))
      (node (ref "Q1") (pin "3") (pinfunction "D_3") (pintype "passive"))
    )
    (net (code "59") (name "Net-(IC3-VOUT+)") (class "Default")
      (node (ref "C16") (pin "1") (pinfunction "1_1") (pintype "passive"))
      (node (ref "IC3") (pin "4") (pinfunction "VOUT+_4") (pintype "bidirectional"))
      (node (ref "R17") (pin "2") (pinfunction "2_2") (pintype "passive"))
      (node (ref "R20") (pin "2") (pinfunction "2_2") (pintype "passive"))
      (node (ref "R25") (pin "2") (pinfunction "2_2") (pintype "passive"))
      (node (ref "R31") (pin "2") (pinfunction "2_2") (pintype "passive"))
      (node (ref "R37") (pin "2") (pinfunction "2_2") (pintype "passive"))
      (node (ref "R42") (pin "2") (pinfunction "2_2") (pintype "passive"))
      (node (ref "R45") (pin "2") (pinfunction "2_2") (pintype "passive"))
      (node (ref "R48") (pin "2") (pinfunction "2_2") (pintype "passive"))
      (node (ref "R65") (pin "1") (pinfunction "1_1") (pintype "passive"))
    )
    (net (code "60") (name "Net-(IC3-VOUT-)") (class "Default")
      (node (ref "C16") (pin "2") (pinfunction "2_2") (pintype "passive"))
      (node (ref "IC3") (pin "3") (pinfunction "VOUT-_3") (pintype "bidirectional"))
      (node (ref "OK1") (pin "2") (pinfunction "C_2") (pintype "passive"))
      (node (ref "OK1") (pin "4") (pinfunction "C_4") (pintype "passive"))
      (node (ref "OK2") (pin "2") (pinfunction "C_2") (pintype "passive"))
      (node (ref "OK2") (pin "4") (pinfunction "C_4") (pintype "passive"))
      (node (ref "OK3") (pin "2") (pinfunction "C_2") (pintype "passive"))
      (node (ref "OK3") (pin "4") (pinfunction "C_4") (pintype "passive"))
      (node (ref "OK4") (pin "2") (pinfunction "C_2") (pintype "passive"))
      (node (ref "OK4") (pin "4") (pinfunction "C_4") (pintype "passive"))
      (node (ref "OK5") (pin "2") (pinfunction "C_2") (pintype "passive"))
      (node (ref "OK5") (pin "4") (pinfunction "C_4") (pintype "passive"))
      (node (ref "OK6") (pin "2") (pinfunction "C_2") (pintype "passive"))
      (node (ref "OK6") (pin "4") (pinfunction "C_4") (pintype "passive"))
      (node (ref "OK7") (pin "2") (pinfunction "C_2") (pintype "passive"))
      (node (ref "OK7") (pin "4") (pinfunction "C_4") (pintype "passive"))
      (node (ref "OK8") (pin "2") (pinfunction "C_2") (pintype "passive"))
      (node (ref "OK8") (pin "4") (pinfunction "C_4") (pintype "passive"))
      (node (ref "OK9") (pin "2") (pinfunction "C_2") (pintype "passive"))
      (node (ref "TVS10") (pin "A") (pinfunction "A_A") (pintype "passive"))
      (node (ref "TVS11") (pin "A") (pinfunction "A_A") (pintype "passive"))
      (node (ref "TVS12") (pin "A") (pinfunction "A_A") (pintype "passive"))
      (node (ref "TVS13") (pin "A") (pinfunction "A_A") (pintype "passive"))
      (node (ref "TVS14") (pin "A") (pinfunction "A_A") (pintype "passive"))
      (node (ref "TVS15") (pin "A") (pinfunction "A_A") (pintype "passive"))
      (node (ref "TVS16") (pin "A") (pinfunction "A_A") (pintype "passive"))
      (node (ref "TVS17") (pin "A") (pinfunction "A_A") (pintype "passive"))
      (node (ref "TVS18") (pin "A") (pinfunction "A_A") (pintype "passive"))
      (node (ref "TVS3") (pin "A") (pinfunction "A_A") (pintype "passive"))
      (node (ref "TVS4") (pin "A") (pinfunction "A_A") (pintype "passive"))
      (node (ref "TVS5") (pin "A") (pinfunction "A_A") (pintype "passive"))
      (node (ref "TVS6") (pin "A") (pinfunction "A_A") (pintype "passive"))
      (node (ref "TVS7") (pin "A") (pinfunction "A_A") (pintype "passive"))
      (node (ref "TVS8") (pin "A") (pinfunction "A_A") (pintype "passive"))
      (node (ref "TVS9") (pin "A") (pinfunction "A_A") (pintype "passive"))
    )
    (net (code "61") (name "Net-(IC5-INTA)") (class "Default")
      (node (ref "IC5") (pin "19") (pinfunction "INTA_19") (pintype "bidirectional"))
      (node (ref "X0") (pin "26") (pinfunction "SIM_DET/PA_EINT10/PA10_26") (pintype "bidirectional"))
    )
    (net (code "62") (name "Net-(IC6-BST)") (class "Default")
      (node (ref "C8") (pin "1") (pinfunction "1_1") (pintype "passive"))
      (node (ref "IC6") (pin "6") (pinfunction "BST_6") (pintype "input"))
    )
    (net (code "63") (name "Net-(IC6-FB)") (class "Default")
      (node (ref "IC6") (pin "4") (pinfunction "FB_4") (pintype "input"))
      (node (ref "R10") (pin "2") (pinfunction "2_2") (pintype "passive"))
      (node (ref "R11") (pin "2") (pinfunction "2_2") (pintype "passive"))
    )
    (net (code "64") (name "Net-(IC6-SW)") (class "Default")
      (node (ref "C8") (pin "2") (pinfunction "2_2") (pintype "passive"))
      (node (ref "IC6") (pin "2") (pinfunction "SW_2") (pintype "passive"))
      (node (ref "L4.7") (pin "P$1") (pinfunction "1_P$1") (pintype "passive"))
    )
    (net (code "65") (name "Net-(L4.7-2)") (class "Default")
      (node (ref "C14") (pin "+") (pinfunction "+_+") (pintype "passive"))
      (node (ref "C22") (pin "2") (pinfunction "2_2") (pintype "passive"))
      (node (ref "C9") (pin "2") (pinfunction "2_2") (pintype "passive"))
      (node (ref "L4.7") (pin "P$2") (pinfunction "2_P$2") (pintype "passive"))
      (node (ref "R11") (pin "1") (pinfunction "1_1") (pintype "passive"))
      (node (ref "R5") (pin "2") (pinfunction "2_2") (pintype "passive"))
      (node (ref "X0") (pin "2") (pinfunction "5V_2") (pintype "power_in"))
      (node (ref "X0") (pin "4") (pinfunction "5V_4") (pintype "power_in"))
    )
    (net (code "66") (name "Net-(OK1A-A)") (class "Default")
      (node (ref "OK1") (pin "1") (pinfunction "A_1") (pintype "passive"))
      (node (ref "R16") (pin "2") (pinfunction "2_2") (pintype "passive"))
    )
    (net (code "67") (name "Net-(OK1B-A)") (class "Default")
      (node (ref "OK1") (pin "3") (pinfunction "A_3") (pintype "passive"))
      (node (ref "R15") (pin "2") (pinfunction "2_2") (pintype "passive"))
    )
    (net (code "68") (name "Net-(OK2A-A)") (class "Default")
      (node (ref "OK2") (pin "1") (pinfunction "A_1") (pintype "passive"))
      (node (ref "R19") (pin "2") (pinfunction "2_2") (pintype "passive"))
    )
    (net (code "69") (name "Net-(OK2B-A)") (class "Default")
      (node (ref "OK2") (pin "3") (pinfunction "A_3") (pintype "passive"))
      (node (ref "R18") (pin "2") (pinfunction "2_2") (pintype "passive"))
    )
    (net (code "70") (name "Net-(OK3A-A)") (class "Default")
      (node (ref "OK3") (pin "1") (pinfunction "A_1") (pintype "passive"))
      (node (ref "R24") (pin "2") (pinfunction "2_2") (pintype "passive"))
    )
    (net (code "71") (name "Net-(OK3B-A)") (class "Default")
      (node (ref "OK3") (pin "3") (pinfunction "A_3") (pintype "passive"))
      (node (ref "R21") (pin "2") (pinfunction "2_2") (pintype "passive"))
    )
    (net (code "72") (name "Net-(OK4A-A)") (class "Default")
      (node (ref "OK4") (pin "1") (pinfunction "A_1") (pintype "passive"))
      (node (ref "R27") (pin "2") (pinfunction "2_2") (pintype "passive"))
    )
    (net (code "73") (name "Net-(OK4B-A)") (class "Default")
      (node (ref "OK4") (pin "3") (pinfunction "A_3") (pintype "passive"))
      (node (ref "R26") (pin "2") (pinfunction "2_2") (pintype "passive"))
    )
    (net (code "74") (name "Net-(OK5A-A)") (class "Default")
      (node (ref "OK5") (pin "1") (pinfunction "A_1") (pintype "passive"))
      (node (ref "R36") (pin "2") (pinfunction "2_2") (pintype "passive"))
    )
    (net (code "75") (name "Net-(OK5B-A)") (class "Default")
      (node (ref "OK5") (pin "3") (pinfunction "A_3") (pintype "passive"))
      (node (ref "R32") (pin "2") (pinfunction "2_2") (pintype "passive"))
    )
    (net (code "76") (name "Net-(OK6A-A)") (class "Default")
      (node (ref "OK6") (pin "1") (pinfunction "A_1") (pintype "passive"))
      (node (ref "R39") (pin "2") (pinfunction "2_2") (pintype "passive"))
    )
    (net (code "77") (name "Net-(OK6B-A)") (class "Default")
      (node (ref "OK6") (pin "3") (pinfunction "A_3") (pintype "passive"))
      (node (ref "R38") (pin "2") (pinfunction "2_2") (pintype "passive"))
    )
    (net (code "78") (name "Net-(OK7A-A)") (class "Default")
      (node (ref "OK7") (pin "1") (pinfunction "A_1") (pintype "passive"))
      (node (ref "R44") (pin "2") (pinfunction "2_2") (pintype "passive"))
    )
    (net (code "79") (name "Net-(OK7B-A)") (class "Default")
      (node (ref "OK7") (pin "3") (pinfunction "A_3") (pintype "passive"))
      (node (ref "R43") (pin "2") (pinfunction "2_2") (pintype "passive"))
    )
    (net (code "80") (name "Net-(OK8A-A)") (class "Default")
      (node (ref "OK8") (pin "1") (pinfunction "A_1") (pintype "passive"))
      (node (ref "R47") (pin "2") (pinfunction "2_2") (pintype "passive"))
    )
    (net (code "81") (name "Net-(OK8B-A)") (class "Default")
      (node (ref "OK8") (pin "3") (pinfunction "A_3") (pintype "passive"))
      (node (ref "R46") (pin "2") (pinfunction "2_2") (pintype "passive"))
    )
    (net (code "82") (name "Net-(OK9A-A)") (class "Default")
      (node (ref "OK9") (pin "1") (pinfunction "A_1") (pintype "passive"))
      (node (ref "R65") (pin "2") (pinfunction "2_2") (pintype "passive"))
    )
    (net (code "83") (name "Net-(Q1-G)") (class "Default")
      (node (ref "Q1") (pin "1") (pinfunction "G_1") (pintype "passive"))
      (node (ref "R67") (pin "1") (pinfunction "1_1") (pintype "passive"))
    )
    (net (code "84") (name "Net-(X0-UART1_RX{slash}PG07)") (class "Default")
      (node (ref "R1") (pin "2") (pinfunction "2_2") (pintype "passive"))
      (node (ref "R3") (pin "2") (pinfunction "2_2") (pintype "passive"))
      (node (ref "UART") (pin "2") (pinfunction "2_2") (pintype "passive"))
      (node (ref "X0") (pin "10") (pinfunction "UART1_RX/PG07_10") (pintype "bidirectional"))
    )
    (net (code "85") (name "Net-(X0-UART1_TX{slash}PG06)") (class "Default")
      (node (ref "R2") (pin "2") (pinfunction "2_2") (pintype "passive"))
      (node (ref "R4") (pin "2") (pinfunction "2_2") (pintype "passive"))
      (node (ref "UART") (pin "1") (pinfunction "1_1") (pintype "passive"))
      (node (ref "X0") (pin "8") (pinfunction "UART1_TX/PG06_8") (pintype "bidirectional"))
    )
    (net (code "86") (name "Net-(X1A-KL)") (class "Default")
      (node (ref "R21") (pin "1") (pinfunction "1_1") (pintype "passive"))
      (node (ref "TVS7") (pin "C") (pinfunction "C_C") (pintype "passive"))
      (node (ref "X1") (pin "1") (pinfunction "KL_1") (pintype "passive"))
    )
    (net (code "87") (name "Net-(X1B-KL)") (class "Default")
      (node (ref "R24") (pin "1") (pinfunction "1_1") (pintype "passive"))
      (node (ref "TVS8") (pin "C") (pinfunction "C_C") (pintype "passive"))
      (node (ref "X1") (pin "2") (pinfunction "KL_2") (pintype "passive"))
    )
    (net (code "88") (name "Net-(X1C-KL)") (class "Default")
      (node (ref "R25") (pin "1") (pinfunction "1_1") (pintype "passive"))
      (node (ref "X1") (pin "3") (pinfunction "KL_3") (pintype "passive"))
    )
    (net (code "89") (name "Net-(X2A-KL)") (class "Default")
      (node (ref "R43") (pin "1") (pinfunction "1_1") (pintype "passive"))
      (node (ref "TVS15") (pin "C") (pinfunction "C_C") (pintype "passive"))
      (node (ref "X2") (pin "1") (pinfunction "KL_1") (pintype "passive"))
    )
    (net (code "90") (name "Net-(X2B-KL)") (class "Default")
      (node (ref "R44") (pin "1") (pinfunction "1_1") (pintype "passive"))
      (node (ref "TVS16") (pin "C") (pinfunction "C_C") (pintype "passive"))
      (node (ref "X2") (pin "2") (pinfunction "KL_2") (pintype "passive"))
    )
    (net (code "91") (name "Net-(X2C-KL)") (class "Default")
      (node (ref "R45") (pin "1") (pinfunction "1_1") (pintype "passive"))
      (node (ref "X2") (pin "3") (pinfunction "KL_3") (pintype "passive"))
    )
    (net (code "92") (name "Net-(X3A-KL)") (class "Default")
      (node (ref "R38") (pin "1") (pinfunction "1_1") (pintype "passive"))
      (node (ref "TVS13") (pin "C") (pinfunction "C_C") (pintype "passive"))
      (node (ref "X3") (pin "1") (pinfunction "KL_1") (pintype "passive"))
    )
    (net (code "93") (name "Net-(X3B-KL)") (class "Default")
      (node (ref "R39") (pin "1") (pinfunction "1_1") (pintype "passive"))
      (node (ref "TVS14") (pin "C") (pinfunction "C_C") (pintype "passive"))
      (node (ref "X3") (pin "2") (pinfunction "KL_2") (pintype "passive"))
    )
    (net (code "94") (name "Net-(X3C-KL)") (class "Default")
      (node (ref "R42") (pin "1") (pinfunction "1_1") (pintype "passive"))
      (node (ref "X3") (pin "3") (pinfunction "KL_3") (pintype "passive"))
    )
    (net (code "95") (name "Net-(X4A-KL)") (class "Default")
      (node (ref "R15") (pin "1") (pinfunction "1_1") (pintype "passive"))
      (node (ref "TVS3") (pin "C") (pinfunction "C_C") (pintype "passive"))
      (node (ref "X4") (pin "1") (pinfunction "KL_1") (pintype "passive"))
    )
    (net (code "96") (name "Net-(X4B-KL)") (class "Default")
      (node (ref "R16") (pin "1") (pinfunction "1_1") (pintype "passive"))
      (node (ref "TVS4") (pin "C") (pinfunction "C_C") (pintype "passive"))
      (node (ref "X4") (pin "2") (pinfunction "KL_2") (pintype "passive"))
    )
    (net (code "97") (name "Net-(X4C-KL)") (class "Default")
      (node (ref "R17") (pin "1") (pinfunction "1_1") (pintype "passive"))
      (node (ref "X4") (pin "3") (pinfunction "KL_3") (pintype "passive"))
    )
    (net (code "98") (name "Net-(X5A-KL)") (class "Default")
      (node (ref "R26") (pin "1") (pinfunction "1_1") (pintype "passive"))
      (node (ref "TVS9") (pin "C") (pinfunction "C_C") (pintype "passive"))
      (node (ref "X5") (pin "1") (pinfunction "KL_1") (pintype "passive"))
    )
    (net (code "99") (name "Net-(X5B-KL)") (class "Default")
      (node (ref "R27") (pin "1") (pinfunction "1_1") (pintype "passive"))
      (node (ref "TVS10") (pin "C") (pinfunction "C_C") (pintype "passive"))
      (node (ref "X5") (pin "2") (pinfunction "KL_2") (pintype "passive"))
    )
    (net (code "100") (name "Net-(X5C-KL)") (class "Default")
      (node (ref "R31") (pin "1") (pinfunction "1_1") (pintype "passive"))
      (node (ref "X5") (pin "3") (pinfunction "KL_3") (pintype "passive"))
    )
    (net (code "101") (name "Net-(X6A-KL)") (class "Default")
      (node (ref "R46") (pin "1") (pinfunction "1_1") (pintype "passive"))
      (node (ref "TVS17") (pin "C") (pinfunction "C_C") (pintype "passive"))
      (node (ref "X6") (pin "1") (pinfunction "KL_1") (pintype "passive"))
    )
    (net (code "102") (name "Net-(X6B-KL)") (class "Default")
      (node (ref "R47") (pin "1") (pinfunction "1_1") (pintype "passive"))
      (node (ref "TVS18") (pin "C") (pinfunction "C_C") (pintype "passive"))
      (node (ref "X6") (pin "2") (pinfunction "KL_2") (pintype "passive"))
    )
    (net (code "103") (name "Net-(X6C-KL)") (class "Default")
      (node (ref "R48") (pin "1") (pinfunction "1_1") (pintype "passive"))
      (node (ref "X6") (pin "3") (pinfunction "KL_3") (pintype "passive"))
    )
    (net (code "104") (name "Net-(X7A-KL)") (class "Default")
      (node (ref "R18") (pin "1") (pinfunction "1_1") (pintype "passive"))
      (node (ref "TVS5") (pin "C") (pinfunction "C_C") (pintype "passive"))
      (node (ref "X7") (pin "1") (pinfunction "KL_1") (pintype "passive"))
    )
    (net (code "105") (name "Net-(X7B-KL)") (class "Default")
      (node (ref "R19") (pin "1") (pinfunction "1_1") (pintype "passive"))
      (node (ref "TVS6") (pin "C") (pinfunction "C_C") (pintype "passive"))
      (node (ref "X7") (pin "2") (pinfunction "KL_2") (pintype "passive"))
    )
    (net (code "106") (name "Net-(X7C-KL)") (class "Default")
      (node (ref "R20") (pin "1") (pinfunction "1_1") (pintype "passive"))
      (node (ref "X7") (pin "3") (pinfunction "KL_3") (pintype "passive"))
    )
    (net (code "107") (name "Net-(X8A-KL)") (class "Default")
      (node (ref "R32") (pin "1") (pinfunction "1_1") (pintype "passive"))
      (node (ref "TVS11") (pin "C") (pinfunction "C_C") (pintype "passive"))
      (node (ref "X8") (pin "1") (pinfunction "KL_1") (pintype "passive"))
    )
    (net (code "108") (name "Net-(X8B-KL)") (class "Default")
      (node (ref "R36") (pin "1") (pinfunction "1_1") (pintype "passive"))
      (node (ref "TVS12") (pin "C") (pinfunction "C_C") (pintype "passive"))
      (node (ref "X8") (pin "2") (pinfunction "KL_2") (pintype "passive"))
    )
    (net (code "109") (name "Net-(X8C-KL)") (class "Default")
      (node (ref "R37") (pin "1") (pinfunction "1_1") (pintype "passive"))
      (node (ref "X8") (pin "3") (pinfunction "KL_3") (pintype "passive"))
    )
    (net (code "110") (name "Net-(X9A-KL)") (class "Default")
      (node (ref "D10") (pin "A") (pinfunction "A_A") (pintype "passive"))
      (node (ref "R30") (pin "1") (pinfunction "1_1") (pintype "passive"))
      (node (ref "X9") (pin "1") (pinfunction "KL_1") (pintype "passive"))
    )
    (net (code "111") (name "Net-(X9B-KL)") (class "Default")
      (node (ref "D5") (pin "A") (pinfunction "A_A") (pintype "passive"))
      (node (ref "X9") (pin "2") (pinfunction "KL_2") (pintype "passive"))
    )
    (net (code "112") (name "Net-(X10D-KL)") (class "Default")
      (node (ref "C15") (pin "2") (pinfunction "2_2") (pintype "passive"))
      (node (ref "FS1") (pin "1") (pinfunction "1_1") (pintype "passive"))
      (node (ref "X10") (pin "4") (pinfunction "KL_4") (pintype "passive"))
    )
    (net (code "113") (name "unconnected-(IC1-PC2(ADC2{slash}PCINT10)-Pad25)") (class "Default")
      (node (ref "IC1") (pin "25") (pinfunction "PC2(ADC2/PCINT10)_25") (pintype "bidirectional"))
    )
    (net (code "114") (name "unconnected-(IC1-PD7(AIN1{slash}PCINT23)-Pad11)") (class "Default")
      (node (ref "IC1") (pin "11") (pinfunction "PD7(AIN1/PCINT23)_11") (pintype "bidirectional"))
    )
    (net (code "115") (name "unconnected-(IC5-INTB-Pad20)") (class "Default")
      (node (ref "IC5") (pin "20") (pinfunction "INTB_20") (pintype "bidirectional"))
    )
    (net (code "116") (name "unconnected-(IC5-NC-Pad11)") (class "Default")
      (node (ref "IC5") (pin "11") (pinfunction "NC_11") (pintype "bidirectional"))
    )
    (net (code "117") (name "unconnected-(IC5-NC-Pad14)") (class "Default")
      (node (ref "IC5") (pin "14") (pinfunction "NC_14") (pintype "bidirectional"))
    )
    (net (code "118") (name "unconnected-(IC7-NC-Pad3)") (class "Default")
      (node (ref "IC7") (pin "3") (pinfunction "NC_3") (pintype "no_connect"))
    )
    (net (code "119") (name "unconnected-(OK9B-A-Pad3)") (class "Default")
      (node (ref "OK9") (pin "3") (pinfunction "A_3") (pintype "passive"))
    )
    (net (code "120") (name "unconnected-(OK9B-C-Pad4)") (class "Default")
      (node (ref "OK9") (pin "4") (pinfunction "C_4") (pintype "passive"))
    )
    (net (code "121") (name "unconnected-(OK9B-COL-Pad6)") (class "Default")
      (node (ref "OK9") (pin "6") (pinfunction "COL_6") (pintype "passive"))
    )
    (net (code "122") (name "unconnected-(OK9B-EMIT-Pad5)") (class "Default")
      (node (ref "OK9") (pin "5") (pinfunction "EMIT_5") (pintype "passive"))
    )
    (net (code "123") (name "unconnected-(X0-PA13{slash}SPI1_CS-Pad24)") (class "Default")
      (node (ref "X0") (pin "24") (pinfunction "PA13/SPI1_CS_24") (pintype "bidirectional"))
    )
    (net (code "124") (name "unconnected-(X0-PA14{slash}SPI1_CLK-Pad23)") (class "Default")
      (node (ref "X0") (pin "23") (pinfunction "PA14/SPI1_CLK_23") (pintype "bidirectional"))
    )
    (net (code "125") (name "unconnected-(X0-PA15{slash}SPI1_MOSI-Pad19)") (class "Default")
      (node (ref "X0") (pin "19") (pinfunction "PA15/SPI1_MOSI_19") (pintype "bidirectional"))
    )
    (net (code "126") (name "unconnected-(X0-PA16{slash}SPI1_MISO-Pad21)") (class "Default")
      (node (ref "X0") (pin "21") (pinfunction "PA16/SPI1_MISO_21") (pintype "bidirectional"))
    )
    (net (code "127") (name "unconnected-(X0-PA18{slash}TWI1_SCL-Pad18)") (class "Default")
      (node (ref "X0") (pin "18") (pinfunction "PA18/TWI1_SCL_18") (pintype "bidirectional"))
    )
    (net (code "128") (name "unconnected-(X0-PA19{slash}TWI1_SDA-Pad16)") (class "Default")
      (node (ref "X0") (pin "16") (pinfunction "PA19/TWI1_SDA_16") (pintype "bidirectional"))
    )
    (net (code "129") (name "unconnected-(X0-UART2_CTS{slash}PA03-Pad15)") (class "Default")
      (node (ref "X0") (pin "15") (pinfunction "UART2_CTS/PA03_15") (pintype "bidirectional"))
    )
  )
)
